# main_board.net
KiCad netlist of a schematic drawn in EAGLE
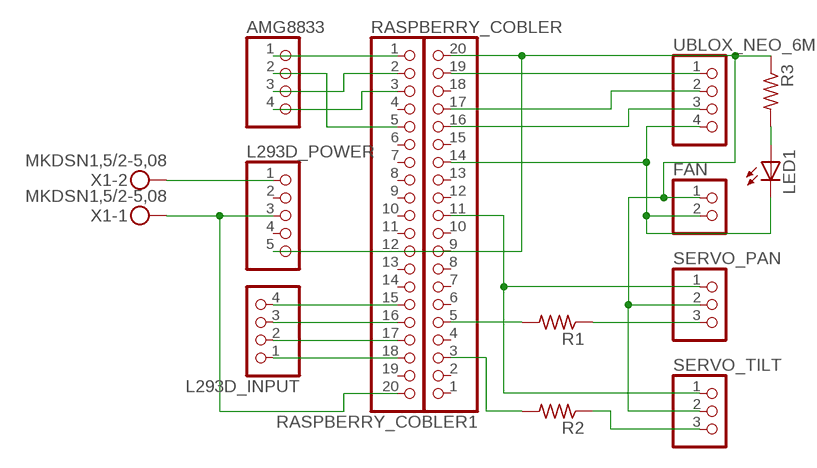
[diagram p0: schematic, sheet 1]

(export (version "E")
  (design (tool "Eeschema 10.0.6"))
  (components
    (comp (ref "AMG8833")
      (value "PINHD-1X4")
      (footprint "eagle-import:1X04")
      (libsource (lib "eagle-import") (part "PINHD-1X4"))
    )
    (comp (ref "FAN")
      (value "PINHD-1X2")
      (footprint "eagle-import:1X02")
      (libsource (lib "eagle-import") (part "PINHD-1X2"))
    )
    (comp (ref "L293D_INPUT")
      (value "PINHD-1X4")
      (footprint "eagle-import:1X04")
      (libsource (lib "eagle-import") (part "PINHD-1X4"))
    )
    (comp (ref "L293D_POWER")
      (value "PINHD-1X5")
      (footprint "eagle-import:1X05")
      (libsource (lib "eagle-import") (part "PINHD-1X5"))
    )
    (comp (ref "LED1")
      (value "LED5MM")
      (footprint "eagle-import:LED5MM")
      (libsource (lib "eagle-import") (part "LED5MM"))
    )
    (comp (ref "R1")
      (value "R-US_0207/10")
      (footprint "eagle-import:0207_10")
      (libsource (lib "eagle-import") (part "R-US_0207/10"))
    )
    (comp (ref "R2")
      (value "R-US_0207/10")
      (footprint "eagle-import:0207_10")
      (libsource (lib "eagle-import") (part "R-US_0207/10"))
    )
    (comp (ref "R3")
      (value "R-US_0207/10")
      (footprint "eagle-import:0207_10")
      (libsource (lib "eagle-import") (part "R-US_0207/10"))
    )
    (comp (ref "RASPBERRY_COBLER")
      (value "PINHD-1X20")
      (footprint "eagle-import:1X20")
      (libsource (lib "eagle-import") (part "PINHD-1X20"))
    )
    (comp (ref "RASPBERRY_COBLER1")
      (value "PINHD-1X20")
      (footprint "eagle-import:1X20")
      (libsource (lib "eagle-import") (part "PINHD-1X20"))
    )
    (comp (ref "SERVO_PAN")
      (value "PINHD-1X3")
      (footprint "eagle-import:1X03")
      (libsource (lib "eagle-import") (part "PINHD-1X3"))
    )
    (comp (ref "SERVO_TILT")
      (value "PINHD-1X3")
      (footprint "eagle-import:1X03")
      (libsource (lib "eagle-import") (part "PINHD-1X3"))
    )
    (comp (ref "UBLOX_NEO_6M")
      (value "PINHD-1X4")
      (footprint "eagle-import:1X04")
      (libsource (lib "eagle-import") (part "PINHD-1X4"))
    )
    (comp (ref "X1")
      (value "MKDSN1,5/2-5,08")
      (footprint "eagle-import:MKDSN1,5_2-5,08")
      (libsource (lib "eagle-import") (part "MKDSN1,5/2-5,08"))
    )
  )
  (nets
    (net (code "1") (name "/GND") (class "Default")
      (node (ref "AMG8833") (pin "2") (pinfunction "2_2") (pintype "passive"))
      (node (ref "FAN") (pin "2") (pinfunction "2_2") (pintype "passive"))
      (node (ref "L293D_POWER") (pin "3") (pinfunction "3_3") (pintype "passive"))
      (node (ref "LED1") (pin "K") (pinfunction "C_K") (pintype "passive"))
      (node (ref "RASPBERRY_COBLER") (pin "20") (pinfunction "20_20") (pintype "passive"))
      (node (ref "RASPBERRY_COBLER") (pin "5") (pinfunction "5_5") (pintype "passive"))
      (node (ref "RASPBERRY_COBLER1") (pin "11") (pinfunction "11_11") (pintype "passive"))
      (node (ref "RASPBERRY_COBLER1") (pin "14") (pinfunction "14_14") (pintype "passive"))
      (node (ref "SERVO_PAN") (pin "1") (pinfunction "1_1") (pintype "passive"))
      (node (ref "SERVO_TILT") (pin "1") (pinfunction "1_1") (pintype "passive"))
      (node (ref "UBLOX_NEO_6M") (pin "4") (pinfunction "4_4") (pintype "passive"))
      (node (ref "X1") (pin "1") (pinfunction "KL_1") (pintype "passive"))
    )
    (net (code "2") (name "Net-(AMG8833-Pad1)") (class "Default")
      (node (ref "AMG8833") (pin "1") (pinfunction "1_1") (pintype "passive"))
      (node (ref "RASPBERRY_COBLER") (pin "1") (pinfunction "1_1") (pintype "passive"))
    )
    (net (code "3") (name "Net-(AMG8833-Pad3)") (class "Default")
      (node (ref "AMG8833") (pin "3") (pinfunction "3_3") (pintype "passive"))
      (node (ref "RASPBERRY_COBLER") (pin "2") (pinfunction "2_2") (pintype "passive"))
    )
    (net (code "4") (name "Net-(AMG8833-Pad4)") (class "Default")
      (node (ref "AMG8833") (pin "4") (pinfunction "4_4") (pintype "passive"))
      (node (ref "RASPBERRY_COBLER") (pin "3") (pinfunction "3_3") (pintype "passive"))
    )
    (net (code "5") (name "Net-(FAN-Pad1)") (class "Default")
      (node (ref "FAN") (pin "1") (pinfunction "1_1") (pintype "passive"))
      (node (ref "L293D_POWER") (pin "5") (pinfunction "5_5") (pintype "passive"))
      (node (ref "R3") (pin "1") (pinfunction "1_1") (pintype "passive"))
      (node (ref "RASPBERRY_COBLER1") (pin "20") (pinfunction "20_20") (pintype "passive"))
      (node (ref "SERVO_PAN") (pin "2") (pinfunction "2_2") (pintype "passive"))
      (node (ref "SERVO_TILT") (pin "2") (pinfunction "2_2") (pintype "passive"))
    )
    (net (code "6") (name "Net-(L293D_INPUT-Pad1)") (class "Default")
      (node (ref "L293D_INPUT") (pin "1") (pinfunction "1_1") (pintype "passive"))
      (node (ref "RASPBERRY_COBLER") (pin "18") (pinfunction "18_18") (pintype "passive"))
    )
    (net (code "7") (name "Net-(L293D_INPUT-Pad2)") (class "Default")
      (node (ref "L293D_INPUT") (pin "2") (pinfunction "2_2") (pintype "passive"))
      (node (ref "RASPBERRY_COBLER") (pin "17") (pinfunction "17_17") (pintype "passive"))
    )
    (net (code "8") (name "Net-(L293D_INPUT-Pad3)") (class "Default")
      (node (ref "L293D_INPUT") (pin "3") (pinfunction "3_3") (pintype "passive"))
      (node (ref "RASPBERRY_COBLER") (pin "16") (pinfunction "16_16") (pintype "passive"))
    )
    (net (code "9") (name "Net-(L293D_INPUT-Pad4)") (class "Default")
      (node (ref "L293D_INPUT") (pin "4") (pinfunction "4_4") (pintype "passive"))
      (node (ref "RASPBERRY_COBLER") (pin "15") (pinfunction "15_15") (pintype "passive"))
    )
    (net (code "10") (name "Net-(LED1-PadA)") (class "Default")
      (node (ref "LED1") (pin "A") (pinfunction "A_A") (pintype "passive"))
      (node (ref "R3") (pin "2") (pinfunction "2_2") (pintype "passive"))
    )
    (net (code "11") (name "Net-(R1-Pad1)") (class "Default")
      (node (ref "R1") (pin "1") (pinfunction "1_1") (pintype "passive"))
      (node (ref "SERVO_PAN") (pin "3") (pinfunction "3_3") (pintype "passive"))
    )
    (net (code "12") (name "Net-(R1-Pad2)") (class "Default")
      (node (ref "R1") (pin "2") (pinfunction "2_2") (pintype "passive"))
      (node (ref "RASPBERRY_COBLER1") (pin "5") (pinfunction "5_5") (pintype "passive"))
    )
    (net (code "13") (name "Net-(R2-Pad1)") (class "Default")
      (node (ref "R2") (pin "1") (pinfunction "1_1") (pintype "passive"))
      (node (ref "SERVO_TILT") (pin "3") (pinfunction "3_3") (pintype "passive"))
    )
    (net (code "14") (name "Net-(R2-Pad2)") (class "Default")
      (node (ref "R2") (pin "2") (pinfunction "2_2") (pintype "passive"))
      (node (ref "RASPBERRY_COBLER1") (pin "3") (pinfunction "3_3") (pintype "passive"))
    )
    (net (code "15") (name "Net-(RASPBERRY_COBLER1-Pad16)") (class "Default")
      (node (ref "RASPBERRY_COBLER1") (pin "16") (pinfunction "16_16") (pintype "passive"))
      (node (ref "UBLOX_NEO_6M") (pin "3") (pinfunction "3_3") (pintype "passive"))
    )
    (net (code "16") (name "Net-(RASPBERRY_COBLER1-Pad17)") (class "Default")
      (node (ref "RASPBERRY_COBLER1") (pin "17") (pinfunction "17_17") (pintype "passive"))
      (node (ref "UBLOX_NEO_6M") (pin "2") (pinfunction "2_2") (pintype "passive"))
    )
    (net (code "17") (name "Net-(RASPBERRY_COBLER1-Pad19)") (class "Default")
      (node (ref "RASPBERRY_COBLER1") (pin "19") (pinfunction "19_19") (pintype "passive"))
      (node (ref "UBLOX_NEO_6M") (pin "1") (pinfunction "1_1") (pintype "passive"))
    )
    (net (code "18") (name "Net-(X1B-KL)") (class "Default")
      (node (ref "L293D_POWER") (pin "1") (pinfunction "1_1") (pintype "passive"))
      (node (ref "X1") (pin "2") (pinfunction "KL_2") (pintype "passive"))
    )
    (net (code "19") (name "unconnected-(L293D_POWER-Pad2)") (class "Default")
      (node (ref "L293D_POWER") (pin "2") (pinfunction "2_2") (pintype "passive"))
    )
    (net (code "20") (name "unconnected-(L293D_POWER-Pad4)") (class "Default")
      (node (ref "L293D_POWER") (pin "4") (pinfunction "4_4") (pintype "passive"))
    )
    (net (code "21") (name "unconnected-(RASPBERRY_COBLER-Pad4)") (class "Default")
      (node (ref "RASPBERRY_COBLER") (pin "4") (pinfunction "4_4") (pintype "passive"))
    )
    (net (code "22") (name "unconnected-(RASPBERRY_COBLER-Pad6)") (class "Default")
      (node (ref "RASPBERRY_COBLER") (pin "6") (pinfunction "6_6") (pintype "passive"))
    )
    (net (code "23") (name "unconnected-(RASPBERRY_COBLER-Pad7)") (class "Default")
      (node (ref "RASPBERRY_COBLER") (pin "7") (pinfunction "7_7") (pintype "passive"))
    )
    (net (code "24") (name "unconnected-(RASPBERRY_COBLER-Pad8)") (class "Default")
      (node (ref "RASPBERRY_COBLER") (pin "8") (pinfunction "8_8") (pintype "passive"))
    )
    (net (code "25") (name "unconnected-(RASPBERRY_COBLER-Pad9)") (class "Default")
      (node (ref "RASPBERRY_COBLER") (pin "9") (pinfunction "9_9") (pintype "passive"))
    )
    (net (code "26") (name "unconnected-(RASPBERRY_COBLER-Pad10)") (class "Default")
      (node (ref "RASPBERRY_COBLER") (pin "10") (pinfunction "10_10") (pintype "passive"))
    )
    (net (code "27") (name "unconnected-(RASPBERRY_COBLER-Pad11)") (class "Default")
      (node (ref "RASPBERRY_COBLER") (pin "11") (pinfunction "11_11") (pintype "passive"))
    )
    (net (code "28") (name "unconnected-(RASPBERRY_COBLER-Pad12)") (class "Default")
      (node (ref "RASPBERRY_COBLER") (pin "12") (pinfunction "12_12") (pintype "passive"))
    )
    (net (code "29") (name "unconnected-(RASPBERRY_COBLER-Pad13)") (class "Default")
      (node (ref "RASPBERRY_COBLER") (pin "13") (pinfunction "13_13") (pintype "passive"))
    )
    (net (code "30") (name "unconnected-(RASPBERRY_COBLER-Pad14)") (class "Default")
      (node (ref "RASPBERRY_COBLER") (pin "14") (pinfunction "14_14") (pintype "passive"))
    )
    (net (code "31") (name "unconnected-(RASPBERRY_COBLER-Pad19)") (class "Default")
      (node (ref "RASPBERRY_COBLER") (pin "19") (pinfunction "19_19") (pintype "passive"))
    )
    (net (code "32") (name "unconnected-(RASPBERRY_COBLER1-Pad1)") (class "Default")
      (node (ref "RASPBERRY_COBLER1") (pin "1") (pinfunction "1_1") (pintype "passive"))
    )
    (net (code "33") (name "unconnected-(RASPBERRY_COBLER1-Pad2)") (class "Default")
      (node (ref "RASPBERRY_COBLER1") (pin "2") (pinfunction "2_2") (pintype "passive"))
    )
    (net (code "34") (name "unconnected-(RASPBERRY_COBLER1-Pad4)") (class "Default")
      (node (ref "RASPBERRY_COBLER1") (pin "4") (pinfunction "4_4") (pintype "passive"))
    )
    (net (code "35") (name "unconnected-(RASPBERRY_COBLER1-Pad6)") (class "Default")
      (node (ref "RASPBERRY_COBLER1") (pin "6") (pinfunction "6_6") (pintype "passive"))
    )
    (net (code "36") (name "unconnected-(RASPBERRY_COBLER1-Pad7)") (class "Default")
      (node (ref "RASPBERRY_COBLER1") (pin "7") (pinfunction "7_7") (pintype "passive"))
    )
    (net (code "37") (name "unconnected-(RASPBERRY_COBLER1-Pad8)") (class "Default")
      (node (ref "RASPBERRY_COBLER1") (pin "8") (pinfunction "8_8") (pintype "passive"))
    )
    (net (code "38") (name "unconnected-(RASPBERRY_COBLER1-Pad9)") (class "Default")
      (node (ref "RASPBERRY_COBLER1") (pin "9") (pinfunction "9_9") (pintype "passive"))
    )
    (net (code "39") (name "unconnected-(RASPBERRY_COBLER1-Pad10)") (class "Default")
      (node (ref "RASPBERRY_COBLER1") (pin "10") (pinfunction "10_10") (pintype "passive"))
    )
    (net (code "40") (name "unconnected-(RASPBERRY_COBLER1-Pad12)") (class "Default")
      (node (ref "RASPBERRY_COBLER1") (pin "12") (pinfunction "12_12") (pintype "passive"))
    )
    (net (code "41") (name "unconnected-(RASPBERRY_COBLER1-Pad13)") (class "Default")
      (node (ref "RASPBERRY_COBLER1") (pin "13") (pinfunction "13_13") (pintype "passive"))
    )
    (net (code "42") (name "unconnected-(RASPBERRY_COBLER1-Pad15)") (class "Default")
      (node (ref "RASPBERRY_COBLER1") (pin "15") (pinfunction "15_15") (pintype "passive"))
    )
    (net (code "43") (name "unconnected-(RASPBERRY_COBLER1-Pad18)") (class "Default")
      (node (ref "RASPBERRY_COBLER1") (pin "18") (pinfunction "18_18") (pintype "passive"))
    )
  )
)
